# Esp32_Wroom_Contr_le_de_RFID.net
KiCad netlist of a schematic drawn in Altium Designer
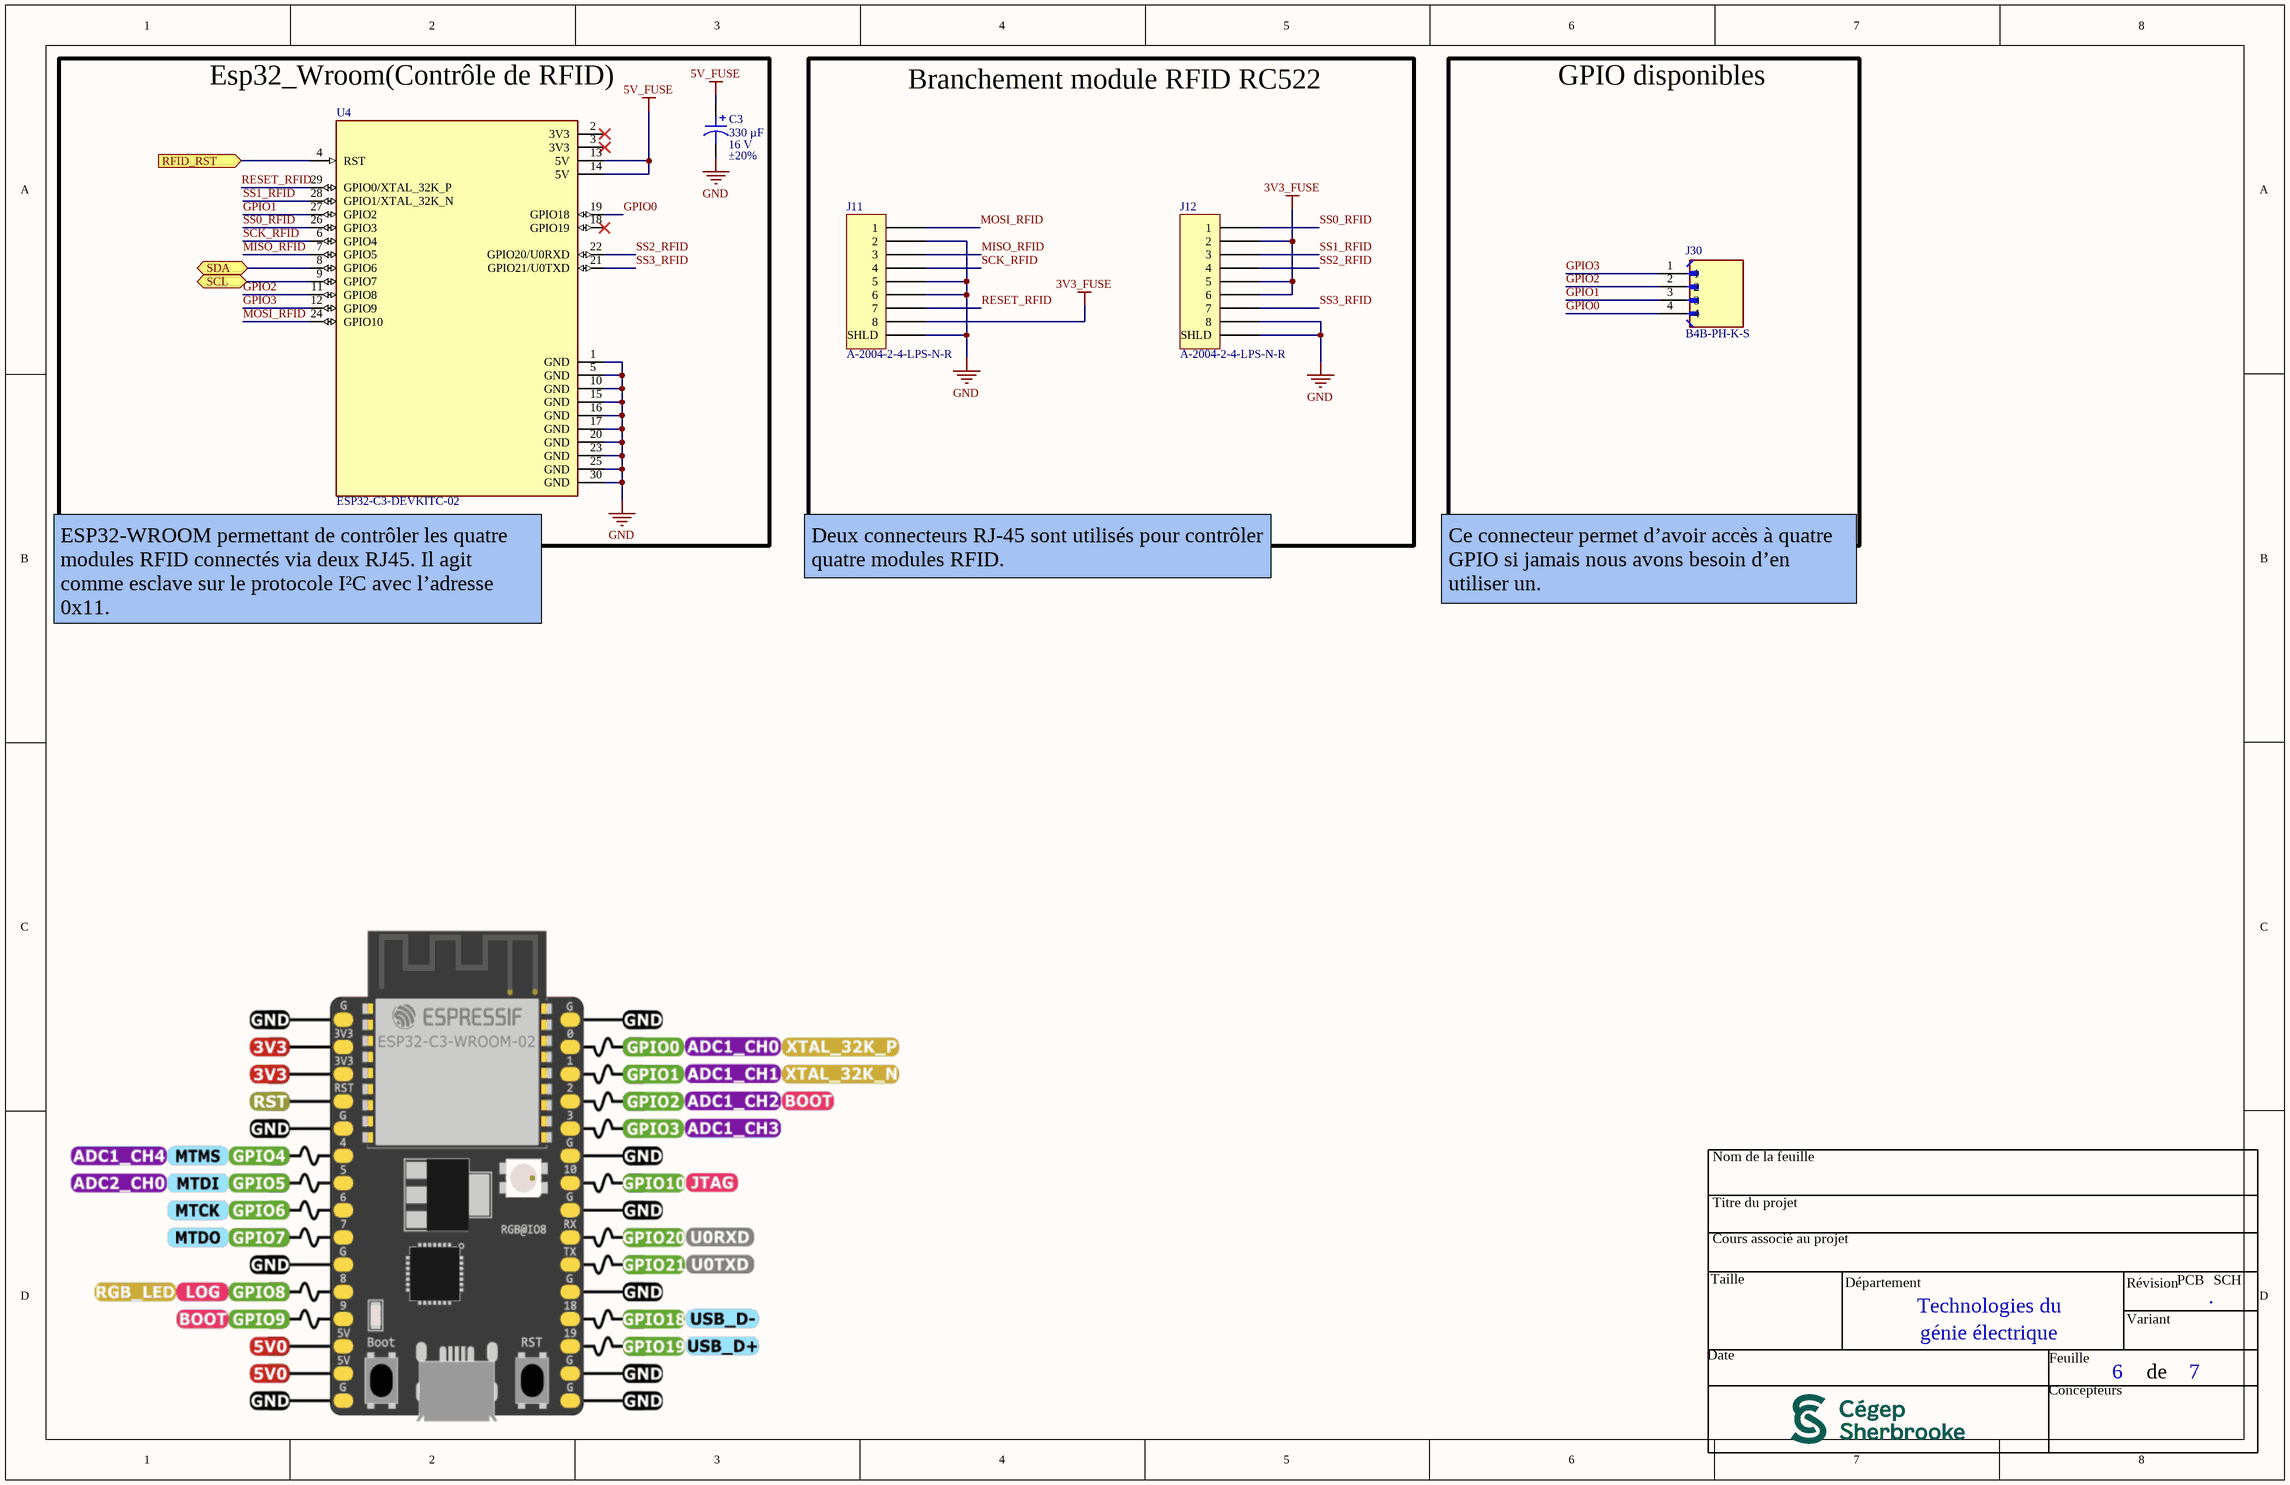
[diagram p0: Esp32_Wroom(Contrôle de RFID).SchDoc]

(export (version "E")
  (design (tool "Eeschema 10.0.6"))
  (components
    (comp (ref "C3")
      (value "330 µF")
      (footprint "CAP ALSMD 8.3MM H10.5MM")
      (description "CAP ALUM 330UF 20% 16V SMD")
      (fields
        (field (name "PART NUMBER") "865060353008")
        (field (name "MANUFACTURER") "Würth Elektronik")
        (field (name "TOLERANCE") "±20%")
        (field (name "VOLTAGE - RATED") "16 V")
      )
      (libsource (lib "Celestial Altium Library - altium_library") (part "Polarised Capacitor"))
    )
    (comp (ref "J11")
      (value "A-2004-2-4-LPS-N-R")
      (footprint "ASSMANN A-2004-2-4-LPS-N-R")
      (description "CONN MOD JACK 8P8C R/A SHIELDED")
      (fields (field (name "MANUFACTURER") "Assmann WSW Components"))
      (libsource (lib "Celestial Altium Library - altium_library") (part "Modular Jack with Shield"))
    )
    (comp (ref "J12")
      (value "A-2004-2-4-LPS-N-R")
      (footprint "ASSMANN A-2004-2-4-LPS-N-R")
      (description "CONN MOD JACK 8P8C R/A SHIELDED")
      (fields (field (name "MANUFACTURER") "Assmann WSW Components"))
      (libsource (lib "Celestial Altium Library - altium_library") (part "Modular Jack with Shield"))
    )
    (comp (ref "J30")
      (value "B4B-PH-K-S")
      (footprint "JST_B4B-PH-K-S")
      (fields (field (name "MF") "{'manufacturer': u'JST Sales America Inc.'}"))
      (libsource (lib "B4B-PH-K-S") (part "B4B-PH-K-S"))
    )
    (comp (ref "U4")
      (value "ESP32-C3-DEVKITC-02")
      (footprint "XCVR_ESP32-C3-DEVKITC-02")
      (fields (field (name "MF") "Espressif Systems") (field (name "MP") "ESP32-C3-DevKitC-02"))
      (libsource (lib "ESP32-C3-DEVKITC-02") (part "ESP32-C3-DEVKITC-02"))
    )
  )
  (nets
    (net (code "1") (name "/GPIO0") (class "Default")
      (node (ref "J30") (pin "4") (pinfunction "4_4") (pintype "passive"))
      (node (ref "U4") (pin "19") (pinfunction "GPIO18_19") (pintype "bidirectional"))
    )
    (net (code "2") (name "/GPIO1") (class "Default")
      (node (ref "J30") (pin "3") (pinfunction "3_3") (pintype "passive"))
      (node (ref "U4") (pin "27") (pinfunction "GPIO2_27") (pintype "bidirectional"))
    )
    (net (code "3") (name "/GPIO2") (class "Default")
      (node (ref "J30") (pin "2") (pinfunction "2_2") (pintype "passive"))
      (node (ref "U4") (pin "11") (pinfunction "GPIO8_11") (pintype "bidirectional"))
    )
    (net (code "4") (name "/GPIO3") (class "Default")
      (node (ref "J30") (pin "1") (pinfunction "1_1") (pintype "passive"))
      (node (ref "U4") (pin "12") (pinfunction "GPIO9_12") (pintype "bidirectional"))
    )
    (net (code "5") (name "/MISO_RFID") (class "Default")
      (node (ref "J11") (pin "3") (pinfunction "3_3") (pintype "passive"))
      (node (ref "U4") (pin "7") (pinfunction "GPIO5_7") (pintype "bidirectional"))
    )
    (net (code "6") (name "/MOSI_RFID") (class "Default")
      (node (ref "J11") (pin "1") (pinfunction "1_1") (pintype "passive"))
      (node (ref "U4") (pin "24") (pinfunction "GPIO10_24") (pintype "bidirectional"))
    )
    (net (code "7") (name "/RESET_RFID") (class "Default")
      (node (ref "J11") (pin "7") (pinfunction "7_7") (pintype "passive"))
      (node (ref "U4") (pin "29") (pinfunction "GPIO0/XTAL_32K_P_29") (pintype "bidirectional"))
    )
    (net (code "8") (name "/RFID_RST") (class "Default")
      (node (ref "U4") (pin "4") (pinfunction "RST_4") (pintype "input"))
    )
    (net (code "9") (name "/SCK_RFID") (class "Default")
      (node (ref "J11") (pin "4") (pinfunction "4_4") (pintype "passive"))
      (node (ref "U4") (pin "6") (pinfunction "GPIO4_6") (pintype "bidirectional"))
    )
    (net (code "10") (name "/SCL") (class "Default")
      (node (ref "U4") (pin "9") (pinfunction "GPIO7_9") (pintype "bidirectional"))
    )
    (net (code "11") (name "/SDA") (class "Default")
      (node (ref "U4") (pin "8") (pinfunction "GPIO6_8") (pintype "bidirectional"))
    )
    (net (code "12") (name "/SS0_RFID") (class "Default")
      (node (ref "J12") (pin "1") (pinfunction "1_1") (pintype "passive"))
      (node (ref "U4") (pin "26") (pinfunction "GPIO3_26") (pintype "bidirectional"))
    )
    (net (code "13") (name "/SS1_RFID") (class "Default")
      (node (ref "J12") (pin "3") (pinfunction "3_3") (pintype "passive"))
      (node (ref "U4") (pin "28") (pinfunction "GPIO1/XTAL_32K_N_28") (pintype "bidirectional"))
    )
    (net (code "14") (name "/SS2_RFID") (class "Default")
      (node (ref "J12") (pin "4") (pinfunction "4_4") (pintype "passive"))
      (node (ref "U4") (pin "22") (pinfunction "GPIO20/U0RXD_22") (pintype "bidirectional"))
    )
    (net (code "15") (name "/SS3_RFID") (class "Default")
      (node (ref "J12") (pin "7") (pinfunction "7_7") (pintype "passive"))
      (node (ref "U4") (pin "21") (pinfunction "GPIO21/U0TXD_21") (pintype "bidirectional"))
    )
    (net (code "16") (name "3V3_FUSE") (class "Default")
      (node (ref "J11") (pin "8") (pinfunction "8_8") (pintype "passive"))
      (node (ref "J12") (pin "2") (pinfunction "2_2") (pintype "passive"))
      (node (ref "J12") (pin "5") (pinfunction "5_5") (pintype "passive"))
      (node (ref "J12") (pin "6") (pinfunction "6_6") (pintype "passive"))
    )
    (net (code "17") (name "5V_FUSE") (class "Default")
      (node (ref "C3") (pin "1") (pinfunction "1_1") (pintype "passive"))
      (node (ref "U4") (pin "13") (pinfunction "5V_13") (pintype "power_in"))
      (node (ref "U4") (pin "14") (pinfunction "5V_14") (pintype "power_in"))
    )
    (net (code "18") (name "GND") (class "Default")
      (node (ref "C3") (pin "2") (pinfunction "2_2") (pintype "passive"))
      (node (ref "J11") (pin "2") (pinfunction "2_2") (pintype "passive"))
      (node (ref "J11") (pin "5") (pinfunction "5_5") (pintype "passive"))
      (node (ref "J11") (pin "6") (pinfunction "6_6") (pintype "passive"))
      (node (ref "J11") (pin "S") (pinfunction "SHLD_S") (pintype "passive"))
      (node (ref "J12") (pin "8") (pinfunction "8_8") (pintype "passive"))
      (node (ref "J12") (pin "S") (pinfunction "SHLD_S") (pintype "passive"))
      (node (ref "U4") (pin "1") (pinfunction "GND_1") (pintype "power_in"))
      (node (ref "U4") (pin "10") (pinfunction "GND_10") (pintype "power_in"))
      (node (ref "U4") (pin "15") (pinfunction "GND_15") (pintype "power_in"))
      (node (ref "U4") (pin "16") (pinfunction "GND_16") (pintype "power_in"))
      (node (ref "U4") (pin "17") (pinfunction "GND_17") (pintype "power_in"))
      (node (ref "U4") (pin "20") (pinfunction "GND_20") (pintype "power_in"))
      (node (ref "U4") (pin "23") (pinfunction "GND_23") (pintype "power_in"))
      (node (ref "U4") (pin "25") (pinfunction "GND_25") (pintype "power_in"))
      (node (ref "U4") (pin "30") (pinfunction "GND_30") (pintype "power_in"))
      (node (ref "U4") (pin "5") (pinfunction "GND_5") (pintype "power_in"))
    )
    (net (code "19") (name "unconnected-(U4-3V3-Pad2)") (class "Default")
      (node (ref "U4") (pin "2") (pinfunction "3V3_2") (pintype "power_in"))
    )
    (net (code "20") (name "unconnected-(U4-3V3-Pad3)") (class "Default")
      (node (ref "U4") (pin "3") (pinfunction "3V3_3") (pintype "power_in"))
    )
    (net (code "21") (name "unconnected-(U4-GPIO19-Pad18)") (class "Default")
      (node (ref "U4") (pin "18") (pinfunction "GPIO19_18") (pintype "bidirectional+no_connect"))
    )
  )
)
